# 4_BLE-T3_power.net
KiCad netlist of a schematic drawn in Altium Designer
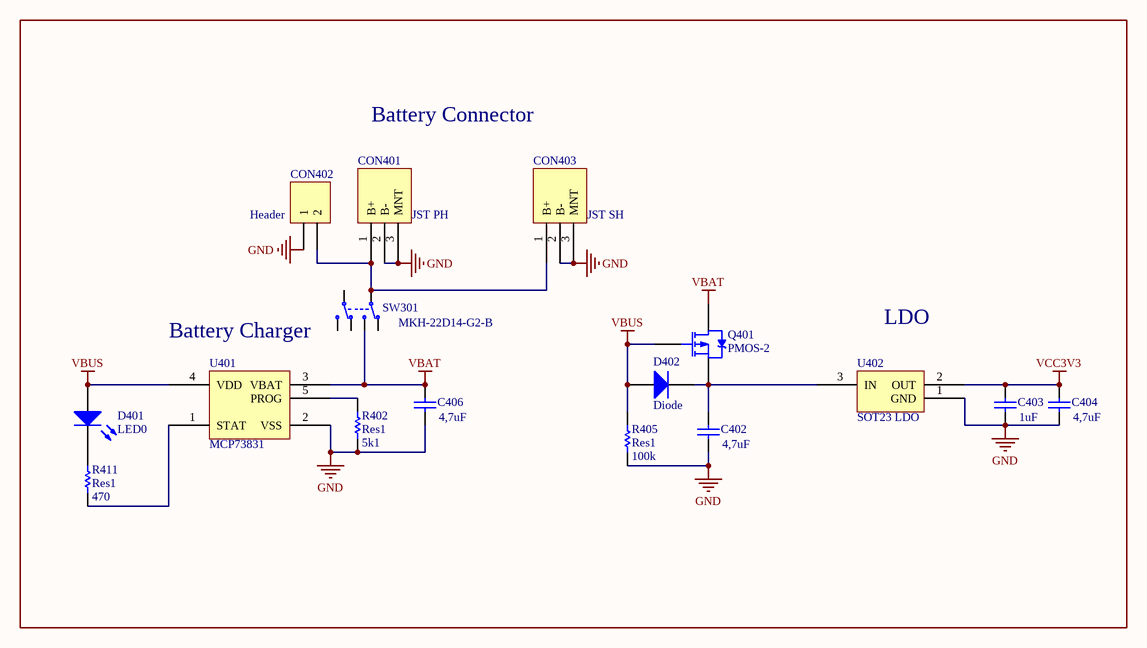
[diagram p0: 4_BLE-T3_power.SchDoc]

(export (version "E")
  (design (tool "Eeschema 10.0.6"))
  (components
    (comp (ref "C402")
      (value "4,7uF")
      (footprint "C0603[1608]")
      (description "Capacitor")
      (fields (field (name "LCSC PART #") "C19666") (field (name "MRF.PART") "CL10A475KO8NNNC"))
      (libsource (lib "Miscellaneous Devices") (part "Cap"))
    )
    (comp (ref "C403")
      (value "1uF")
      (footprint "C0603[1608]")
      (description "Capacitor")
      (fields (field (name "MFG") "KEMET") (field (name "LCSC PART #") "C15849"))
      (libsource (lib "Miscellaneous Devices") (part "Cap"))
    )
    (comp (ref "C404")
      (value "4,7uF")
      (footprint "C0603[1608]")
      (description "Capacitor")
      (fields (field (name "LCSC PART #") "C19666") (field (name "MRF.PART") "CL10A475KO8NNNC"))
      (libsource (lib "Miscellaneous Devices") (part "Cap"))
    )
    (comp (ref "C406")
      (value "4,7uF")
      (footprint "C0603[1608]")
      (description "Capacitor")
      (fields (field (name "LCSC PART #") "C19666") (field (name "MRF.PART") "CL10A475KO8NNNC"))
      (libsource (lib "Miscellaneous Devices") (part "Cap"))
    )
    (comp (ref "CON401")
      (value "JST PH")
      (footprint "JST S2B-PH-SM4-TB")
      (fields (field (name "MFG") "JST Sales America Inc."))
      (libsource (lib "Keebs") (part "JST S2B-PH-SM4-TB"))
    )
    (comp (ref "CON402")
      (value "Header")
      (footprint "HDR1X2")
      (description "Header, 2-Pin")
      (libsource (lib "Miscellaneous Connectors") (part "Header 2"))
    )
    (comp (ref "CON403")
      (value "JST SH")
      (footprint "JST SM02B-SRSS-TB")
      (fields (field (name "MFG") "JST Sales America Inc."))
      (libsource (lib "Keebs") (part "JST S2B-PH-SM4-TB"))
    )
    (comp (ref "D401")
      (value "LED0")
      (footprint "LED0603[1608]")
      (description "Typical INFRARED GaAs LED")
      (fields (field (name "LCSC PART #") "C72038") (field (name "MRF.PART") "19-213/Y2C-CQ2R2L/3T(CY)"))
      (libsource (lib "Miscellaneous Devices") (part "LED0"))
    )
    (comp (ref "D402")
      (value "Diode")
      (footprint "SOD-123")
      (description "Default Diode")
      (fields (field (name "LCSC PART #") "C8598") (field (name "MRF.PART") "B5819W"))
      (libsource (lib "Miscellaneous Devices") (part "Diode"))
    )
    (comp (ref "Q401")
      (value "PMOS-2")
      (footprint "SOT-23-3")
      (description "P-Channel Power MOSFET")
      (fields (field (name "MRF.PART") "SI2301CDS-T1-GE3") (field (name "LCSC PART #") "C10487"))
      (libsource (lib "Miscellaneous Devices") (part "PMOS-2"))
    )
    (comp (ref "R402")
      (value "Res1")
      (footprint "R0603[1608]")
      (description "Resistor")
      (fields
        (field (name "ALTIUM_VALUE") "5k1")
        (field (name "MFG") "Panasonic Electronic Components")
        (field (name "LCSC PART #") "C23186")
      )
      (libsource (lib "Miscellaneous Devices") (part "Res1"))
    )
    (comp (ref "R405")
      (value "Res1")
      (footprint "R0603[1608]")
      (description "Resistor")
      (fields
        (field (name "ALTIUM_VALUE") "100k")
        (field (name "MRF.PART") "0603WAF1003T5E")
        (field (name "LCSC PART #") "C25803")
      )
      (libsource (lib "Miscellaneous Devices") (part "Res1"))
    )
    (comp (ref "R411")
      (value "Res1")
      (footprint "R0603[1608]")
      (description "Resistor")
      (fields
        (field (name "ALTIUM_VALUE") "470")
        (field (name "MFG") "Panasonic Electronic Components")
        (field (name "LCSC PART #") "C23179")
      )
      (libsource (lib "Miscellaneous Devices") (part "Res1"))
    )
    (comp (ref "SW301")
      (value "MKH-22D14-G2-B")
      (footprint "MKH-22D14-G2-B")
      (description "Slide Switch DPDT")
      (fields (field (name "MFG") "Nidec Copal Electronics"))
      (libsource (lib "Keebs") (part "MKH-22D14-G2-B"))
    )
    (comp (ref "U401")
      (value "MCP73831")
      (footprint "SOT-23-5")
      (fields (field (name "LCSC PART #") "C32574") (field (name "MRF.PART") "TP4054"))
      (libsource (lib "Keebs") (part "MCP73831"))
    )
    (comp (ref "U402")
      (value "SOT23 LDO")
      (footprint "SOT-23-3")
      (fields
        (field (name "LCSC PART #") "C5446")
        (field (name "MRF.PART") "XC6206P332MR")
        (field (name "MFG") "Texas Instruments")
      )
      (libsource (lib "Keebs") (part "SOT23 LDO"))
    )
  )
  (nets
    (net (code "1") (name "GND") (class "Default")
      (node (ref "C402") (pin "1") (pinfunction "1_1") (pintype "passive"))
      (node (ref "C403") (pin "1") (pinfunction "1_1") (pintype "passive"))
      (node (ref "C404") (pin "1") (pinfunction "1_1") (pintype "passive"))
      (node (ref "C406") (pin "1") (pinfunction "1_1") (pintype "passive"))
      (node (ref "CON401") (pin "2") (pinfunction "B-_2") (pintype "passive"))
      (node (ref "CON401") (pin "3") (pinfunction "MNT_3") (pintype "passive"))
      (node (ref "CON402") (pin "1") (pinfunction "1_1") (pintype "passive"))
      (node (ref "CON403") (pin "2") (pinfunction "B-_2") (pintype "passive"))
      (node (ref "CON403") (pin "3") (pinfunction "MNT_3") (pintype "passive"))
      (node (ref "R402") (pin "2") (pinfunction "2_2") (pintype "passive"))
      (node (ref "R405") (pin "2") (pinfunction "2_2") (pintype "passive"))
      (node (ref "U401") (pin "2") (pinfunction "VSS_2") (pintype "passive"))
      (node (ref "U402") (pin "1") (pinfunction "GND_1") (pintype "passive"))
    )
    (net (code "2") (name "Net-(CON401-B+)") (class "Default")
      (node (ref "CON401") (pin "1") (pinfunction "B+_1") (pintype "passive"))
      (node (ref "CON402") (pin "2") (pinfunction "2_2") (pintype "passive"))
      (node (ref "CON403") (pin "1") (pinfunction "B+_1") (pintype "passive"))
      (node (ref "SW301") (pin "2") (pinfunction "COM-1_2") (pintype "passive"))
    )
    (net (code "3") (name "Net-(D401-K)") (class "Default")
      (node (ref "D401") (pin "2") (pinfunction "K_2") (pintype "passive"))
      (node (ref "R411") (pin "2") (pinfunction "2_2") (pintype "passive"))
    )
    (net (code "4") (name "Net-(D402-K)") (class "Default")
      (node (ref "C402") (pin "2") (pinfunction "2_2") (pintype "passive"))
      (node (ref "D402") (pin "2") (pinfunction "K_2") (pintype "passive"))
      (node (ref "Q401") (pin "2") (pinfunction "S_2") (pintype "passive"))
      (node (ref "U402") (pin "3") (pinfunction "IN_3") (pintype "passive"))
    )
    (net (code "5") (name "Net-(U401-PROG)") (class "Default")
      (node (ref "R402") (pin "1") (pinfunction "1_1") (pintype "passive"))
      (node (ref "U401") (pin "5") (pinfunction "PROG_5") (pintype "passive"))
    )
    (net (code "6") (name "Net-(U401-STAT)") (class "Default")
      (node (ref "R411") (pin "1") (pinfunction "1_1") (pintype "passive"))
      (node (ref "U401") (pin "1") (pinfunction "STAT_1") (pintype "passive"))
    )
    (net (code "7") (name "VBAT") (class "Default")
      (node (ref "C406") (pin "2") (pinfunction "2_2") (pintype "passive"))
      (node (ref "Q401") (pin "3") (pinfunction "D_3") (pintype "passive"))
      (node (ref "SW301") (pin "1") (pinfunction "N.O-1_1") (pintype "passive"))
      (node (ref "U401") (pin "3") (pinfunction "VBAT_3") (pintype "passive"))
    )
    (net (code "8") (name "VBUS") (class "Default")
      (node (ref "D401") (pin "1") (pinfunction "A_1") (pintype "passive"))
      (node (ref "D402") (pin "1") (pinfunction "A_1") (pintype "passive"))
      (node (ref "Q401") (pin "1") (pinfunction "G_1") (pintype "passive"))
      (node (ref "R405") (pin "1") (pinfunction "1_1") (pintype "passive"))
      (node (ref "U401") (pin "4") (pinfunction "VDD_4") (pintype "passive"))
    )
    (net (code "9") (name "VCC3V3") (class "Default")
      (node (ref "C403") (pin "2") (pinfunction "2_2") (pintype "passive"))
      (node (ref "C404") (pin "2") (pinfunction "2_2") (pintype "passive"))
      (node (ref "U402") (pin "2") (pinfunction "OUT_2") (pintype "passive"))
    )
    (net (code "10") (name "unconnected-(SW301-COM-2-Pad5)") (class "Default")
      (node (ref "SW301") (pin "5") (pinfunction "COM-2_5") (pintype "passive"))
    )
    (net (code "11") (name "unconnected-(SW301-N.C-1-Pad3)") (class "Default")
      (node (ref "SW301") (pin "3") (pinfunction "N.C-1_3") (pintype "passive"))
    )
    (net (code "12") (name "unconnected-(SW301-N.C-2-Pad6)") (class "Default")
      (node (ref "SW301") (pin "6") (pinfunction "N.C-2_6") (pintype "passive"))
    )
    (net (code "13") (name "unconnected-(SW301-N.O-2-Pad4)") (class "Default")
      (node (ref "SW301") (pin "4") (pinfunction "N.O-2_4") (pintype "passive"))
    )
  )
)
